# ST_LINK_Kenzhebek_Aituar.net
KiCad netlist of a schematic drawn in Altium Designer
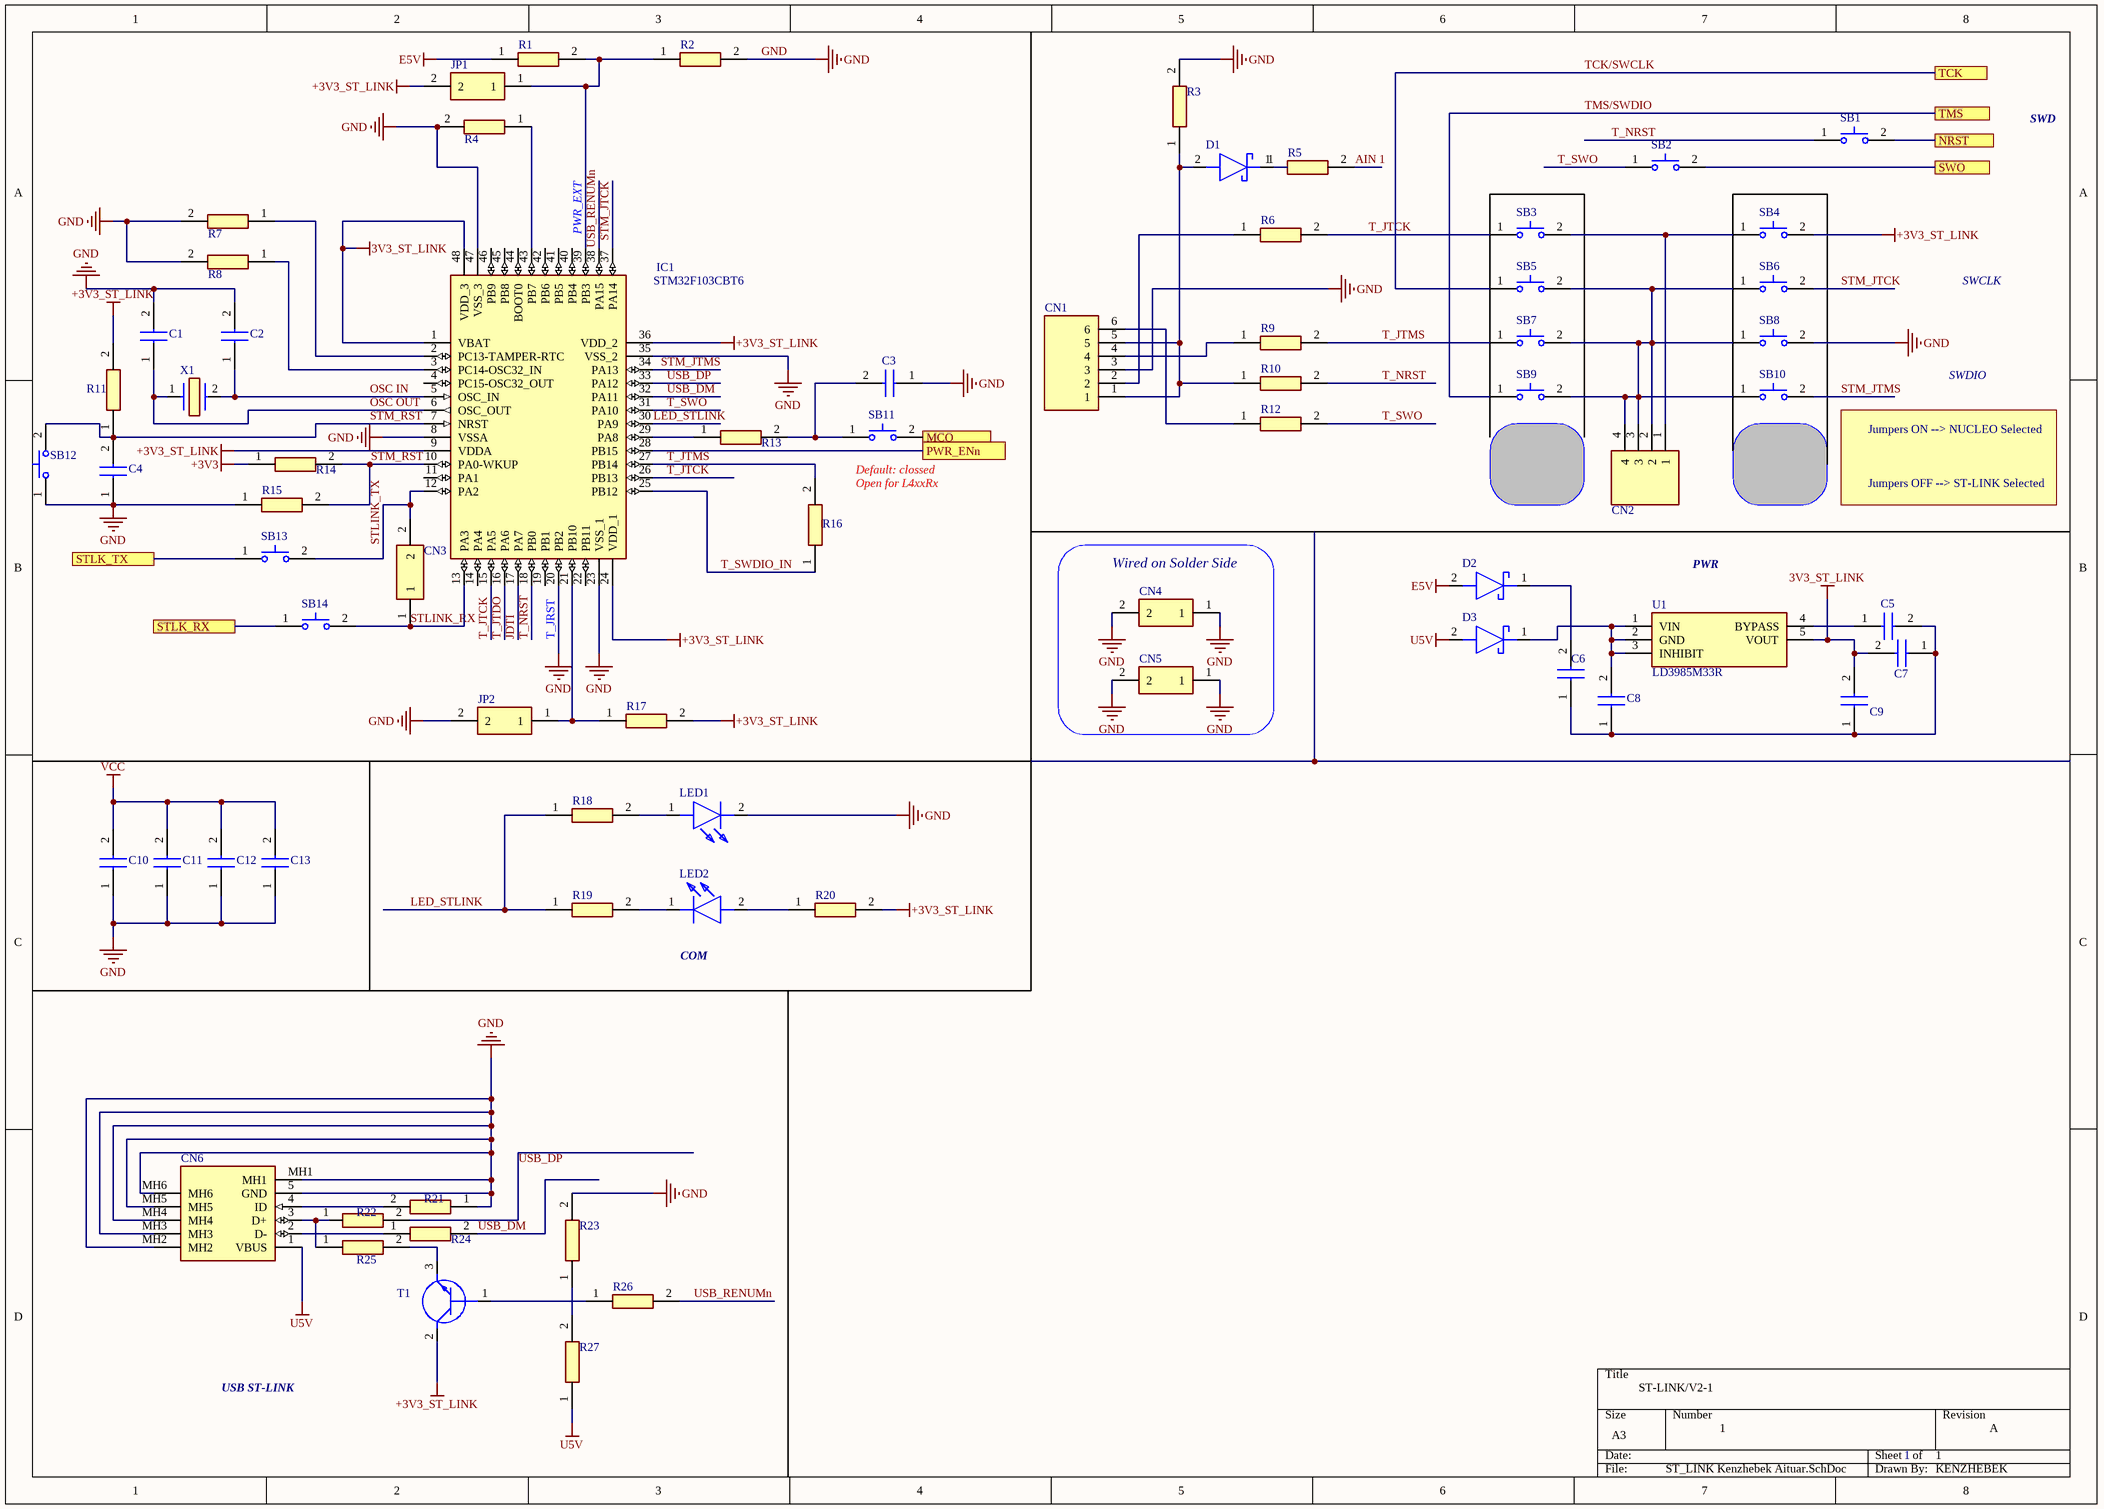
[diagram p0: ST_LINK Kenzhebek Aituar.SchDoc]

(export (version "E")
  (design (tool "Eeschema 10.0.6"))
  (components
    (comp (ref "C1")
      (value "C1206C200KCGACTU")
      (footprint "SamacSys:C1206")
      (description "Capacitor")
      (libsource (lib "*") (part "C1206C200KCGACTU"))
    )
    (comp (ref "C2")
      (value "C1206C200KCGACTU")
      (footprint "SamacSys:C1206")
      (description "Capacitor")
      (libsource (lib "*") (part "C1206C200KCGACTU"))
    )
    (comp (ref "C3")
      (value "C1206C200KCGACTU")
      (footprint "SamacSys:C1206")
      (description "Capacitor")
      (libsource (lib "*") (part "C1206C200KCGACTU"))
    )
    (comp (ref "C4")
      (value "KAM15AR71H104KM")
      (footprint "SamacSys:CAPC1608X90N")
      (description "Capacitor")
      (fields (field (name "MOUSER PART NUMBER") "581-KAM15AR71H104KM"))
      (libsource (lib "*") (part "KAM15AR71H104KM"))
    )
    (comp (ref "C5")
      (value "KGM31GCG2J103JU")
      (footprint "SamacSys:CAPC3316X145N")
      (description "Capacitor")
      (fields (field (name "MOUSER PART NUMBER") "581-KGM31GCG2J103JU"))
      (libsource (lib "*") (part "KGM31GCG2J103JU"))
    )
    (comp (ref "C6")
      (value "MAJCT168BB7105KTEA01")
      (footprint "SamacSys:MAJx16")
      (description "Capacitor")
      (libsource (lib "*") (part "MAJCT168BB7105KTEA01"))
    )
    (comp (ref "C7")
      (value "KAM15AR71H104KM")
      (footprint "SamacSys:CAPC1608X90N")
      (description "Capacitor")
      (fields (field (name "MOUSER PART NUMBER") "581-KAM15AR71H104KM"))
      (libsource (lib "*") (part "KAM15AR71H104KM"))
    )
    (comp (ref "C8")
      (value "KAM15AR71H104KM")
      (footprint "SamacSys:CAPC1608X90N")
      (description "Capacitor")
      (fields (field (name "MOUSER PART NUMBER") "581-KAM15AR71H104KM"))
      (libsource (lib "*") (part "KAM15AR71H104KM"))
    )
    (comp (ref "C9")
      (value "MAJCT168BB7105KTEA01")
      (footprint "SamacSys:MAJx16")
      (description "Capacitor")
      (libsource (lib "*") (part "MAJCT168BB7105KTEA01"))
    )
    (comp (ref "C10")
      (value "KAM15AR71H104KM")
      (footprint "SamacSys:CAPC1608X90N")
      (description "Capacitor")
      (fields (field (name "MOUSER PART NUMBER") "581-KAM15AR71H104KM"))
      (libsource (lib "*") (part "KAM15AR71H104KM"))
    )
    (comp (ref "C11")
      (value "KAM15AR71H104KM")
      (footprint "SamacSys:CAPC1608X90N")
      (description "Capacitor")
      (fields (field (name "MOUSER PART NUMBER") "581-KAM15AR71H104KM"))
      (libsource (lib "*") (part "KAM15AR71H104KM"))
    )
    (comp (ref "C12")
      (value "KAM15AR71H104KM")
      (footprint "SamacSys:CAPC1608X90N")
      (description "Capacitor")
      (fields (field (name "MOUSER PART NUMBER") "581-KAM15AR71H104KM"))
      (libsource (lib "*") (part "KAM15AR71H104KM"))
    )
    (comp (ref "C13")
      (value "KAM15AR71H104KM")
      (footprint "SamacSys:CAPC1608X90N")
      (description "Capacitor")
      (fields (field (name "MOUSER PART NUMBER") "581-KAM15AR71H104KM"))
      (libsource (lib "*") (part "KAM15AR71H104KM"))
    )
    (comp (ref "CN1")
      (value "22-28-4062")
      (footprint "SamacSys:HDRV6W66P0X254_1X6_1524X249X838P")
      (description "Connector")
      (fields (field (name "MOUSER PART NUMBER") "538-22-28-4062"))
      (libsource (lib "*") (part "22-28-4062"))
    )
    (comp (ref "CN2")
      (value "53014-0410")
      (footprint "SamacSys:SHDR4W60P0X200_1X4_1200X435X1000P")
      (description "Connector")
      (fields (field (name "MOUSER PART NUMBER") "538-53014-0410"))
      (libsource (lib "*") (part "53014-0410"))
    )
    (comp (ref "CN3")
      (value "3-647166-2")
      (footprint "SamacSys:36471662")
      (description "Connector")
      (fields (field (name "MOUSER PART NUMBER") "571-3-647166-2"))
      (libsource (lib "*") (part "3-647166-2"))
    )
    (comp (ref "CN4")
      (value "3-647166-2")
      (footprint "SamacSys:36471662")
      (description "Connector")
      (fields (field (name "MOUSER PART NUMBER") "571-3-647166-2"))
      (libsource (lib "") (part "3-647166-2_1"))
    )
    (comp (ref "CN5")
      (value "3-647166-2")
      (footprint "SamacSys:36471662")
      (description "Connector")
      (fields (field (name "MOUSER PART NUMBER") "571-3-647166-2"))
      (libsource (lib "") (part "3-647166-2_1"))
    )
    (comp (ref "CN6")
      (value "204926-1103")
      (footprint "SamacSys:2049261103")
      (description "Connector")
      (fields (field (name "MOUSER PART NUMBER") "538-204926-1103"))
      (libsource (lib "*") (part "204926-1103"))
    )
    (comp (ref "D1")
      (value "BAT60JFILM")
      (footprint "SamacSys:SOD2513X117N")
      (description "Schottky Diode")
      (fields (field (name "MOUSER PART NUMBER") "511-BAT60JFILM"))
      (libsource (lib "*") (part "BAT60JFILM"))
    )
    (comp (ref "D2")
      (value "BAT60JFILM")
      (footprint "SamacSys:SOD2513X117N")
      (description "Schottky Diode")
      (fields (field (name "MOUSER PART NUMBER") "511-BAT60JFILM"))
      (libsource (lib "*") (part "BAT60JFILM"))
    )
    (comp (ref "D3")
      (value "BAT60JFILM")
      (footprint "SamacSys:SOD2513X117N")
      (description "Schottky Diode")
      (fields (field (name "MOUSER PART NUMBER") "511-BAT60JFILM"))
      (libsource (lib "*") (part "BAT60JFILM"))
    )
    (comp (ref "IC1")
      (value "STM32F103CBT6")
      (footprint "SamacSys:QFP50P900X900X160-48N")
      (description "Integrated Circuit")
      (fields (field (name "MOUSER PART NUMBER") "511-STM32F103CBT6"))
      (libsource (lib "*") (part "STM32F103CBT6"))
    )
    (comp (ref "JP1")
      (value "3-647166-2")
      (footprint "SamacSys:36471662")
      (description "Connector")
      (fields (field (name "MOUSER PART NUMBER") "571-3-647166-2"))
      (libsource (lib "") (part "3-647166-2_1"))
    )
    (comp (ref "JP2")
      (value "3-647166-2")
      (footprint "SamacSys:36471662")
      (description "Connector")
      (fields (field (name "MOUSER PART NUMBER") "571-3-647166-2"))
      (libsource (lib "") (part "3-647166-2_1"))
    )
    (comp (ref "LED1")
      (value "C4SMA-RGY-CS4V1BB1")
      (footprint "SamacSys:C4SMARGYCS4V1BB1")
      (description "LED")
      (fields (field (name "MOUSER PART NUMBER") "941-C4SMARGYCS4V1BB1"))
      (libsource (lib "*") (part "C4SMA-RGY-CS4V1BB1"))
    )
    (comp (ref "LED2")
      (value "TLHG5420-ASZ")
      (footprint "SamacSys:TLHG5420ASZ")
      (description "LED")
      (fields (field (name "MOUSER PART NUMBER") "78-TLHG5420-ASZ"))
      (libsource (lib "*") (part "TLHG5420-ASZ"))
    )
    (comp (ref "R1")
      (value "ERA-6ARB272V")
      (footprint "SamacSys:ERA6AEB1020V")
      (description "Resistor")
      (fields (field (name "MOUSER PART NUMBER") "667-ERA-6ARB272V"))
      (libsource (lib "*") (part "ERA-6ARB272V"))
    )
    (comp (ref "R2")
      (value "MCS04020D4701BE000")
      (footprint "SamacSys:RESC1005X37N")
      (description "Resistor")
      (fields (field (name "MOUSER PART NUMBER") "594-MCS04020D4701BE0"))
      (libsource (lib "*") (part "MCS04020D4701BE000"))
    )
    (comp (ref "R3")
      (value "CRM2512QJW-103ELF")
      (footprint "SamacSys:RESC6331X80N")
      (description "Resistor")
      (fields (field (name "MOUSER PART NUMBER") "652-CRM2512QJW-103E"))
      (libsource (lib "") (part "CRM2512QJW-103ELF_1"))
    )
    (comp (ref "R4")
      (value "SFR01MZPF1003")
      (footprint "SamacSys:RESC1005X40N")
      (description "Resistor")
      (fields (field (name "MOUSER PART NUMBER") "755-SFR01MZPF1003"))
      (libsource (lib "*") (part "SFR01MZPF1003"))
    )
    (comp (ref "R5")
      (value "MCS04020C1000FE000")
      (footprint "SamacSys:RESC1005X37N")
      (description "Resistor")
      (fields (field (name "MOUSER PART NUMBER") "594-MCS04020C1000FE0"))
      (libsource (lib "") (part "MCS04020C1000FE000_1"))
    )
    (comp (ref "R6")
      (value "ERA-6AHD220V")
      (footprint "SamacSys:ERA6AEB1020V")
      (description "Resistor")
      (fields (field (name "MOUSER PART NUMBER") "667-ERA-6AHD220V"))
      (libsource (lib "*") (part "ERA-6AHD220V"))
    )
    (comp (ref "R7")
      (value "CRM2512QJW-103ELF")
      (footprint "SamacSys:RESC6331X80N")
      (description "Resistor")
      (fields (field (name "MOUSER PART NUMBER") "652-CRM2512QJW-103E"))
      (libsource (lib "*") (part "CRM2512QJW-103ELF"))
    )
    (comp (ref "R8")
      (value "CRM2512QJW-103ELF")
      (footprint "SamacSys:RESC6331X80N")
      (description "Resistor")
      (fields (field (name "MOUSER PART NUMBER") "652-CRM2512QJW-103E"))
      (libsource (lib "*") (part "CRM2512QJW-103ELF"))
    )
    (comp (ref "R9")
      (value "ERA-6AHD220V")
      (footprint "SamacSys:ERA6AEB1020V")
      (description "Resistor")
      (fields (field (name "MOUSER PART NUMBER") "667-ERA-6AHD220V"))
      (libsource (lib "*") (part "ERA-6AHD220V"))
    )
    (comp (ref "R10")
      (value "ERA-6AHD220V")
      (footprint "SamacSys:ERA6AEB1020V")
      (description "Resistor")
      (fields (field (name "MOUSER PART NUMBER") "667-ERA-6AHD220V"))
      (libsource (lib "*") (part "ERA-6AHD220V"))
    )
    (comp (ref "R11")
      (value "SFR01MZPF1003")
      (footprint "SamacSys:RESC1005X40N")
      (description "Resistor")
      (fields (field (name "MOUSER PART NUMBER") "755-SFR01MZPF1003"))
      (libsource (lib "") (part "SFR01MZPF1003_1"))
    )
    (comp (ref "R12")
      (value "ERA-6AHD220V")
      (footprint "SamacSys:ERA6AEB1020V")
      (description "Resistor")
      (fields (field (name "MOUSER PART NUMBER") "667-ERA-6AHD220V"))
      (libsource (lib "*") (part "ERA-6AHD220V"))
    )
    (comp (ref "R13")
      (value "MCS04020C1000FE000")
      (footprint "SamacSys:RESC1005X37N")
      (description "Resistor")
      (fields (field (name "MOUSER PART NUMBER") "594-MCS04020C1000FE0"))
      (libsource (lib "") (part "MCS04020C1000FE000_1"))
    )
    (comp (ref "R14")
      (value "MCS04020D4701BE000")
      (footprint "SamacSys:RESC1005X37N")
      (description "Resistor")
      (fields (field (name "MOUSER PART NUMBER") "594-MCS04020D4701BE0"))
      (libsource (lib "*") (part "MCS04020D4701BE000"))
    )
    (comp (ref "R15")
      (value "MCS04020D4701BE000")
      (footprint "SamacSys:RESC1005X37N")
      (description "Resistor")
      (fields (field (name "MOUSER PART NUMBER") "594-MCS04020D4701BE0"))
      (libsource (lib "*") (part "MCS04020D4701BE000"))
    )
    (comp (ref "R16")
      (value "MCS04020C1000FE000")
      (footprint "SamacSys:RESC1005X37N")
      (description "Resistor")
      (fields (field (name "MOUSER PART NUMBER") "594-MCS04020C1000FE0"))
      (libsource (lib "*") (part "MCS04020C1000FE000"))
    )
    (comp (ref "R17")
      (value "WSL080500000ZEA9")
      (footprint "SamacSys:RESC2013X84N")
      (description "Resistor")
      (fields (field (name "MOUSER PART NUMBER") "71-WSL080500000ZEA9"))
      (libsource (lib "*") (part "WSL080500000ZEA9"))
    )
    (comp (ref "R18")
      (value "MCS04020C1000FE000")
      (footprint "SamacSys:RESC1005X37N")
      (description "Resistor")
      (fields (field (name "MOUSER PART NUMBER") "594-MCS04020C1000FE0"))
      (libsource (lib "") (part "MCS04020C1000FE000_1"))
    )
    (comp (ref "R19")
      (value "MCS04020C1000FE000")
      (footprint "SamacSys:RESC1005X37N")
      (description "Resistor")
      (fields (field (name "MOUSER PART NUMBER") "594-MCS04020C1000FE0"))
      (libsource (lib "") (part "MCS04020C1000FE000_1"))
    )
    (comp (ref "R20")
      (value "WSL080500000ZEA9")
      (footprint "SamacSys:RESC2013X84N")
      (description "Resistor")
      (fields (field (name "MOUSER PART NUMBER") "71-WSL080500000ZEA9"))
      (libsource (lib "*") (part "WSL080500000ZEA9"))
    )
    (comp (ref "R21")
      (value "SFR01MZPF1003")
      (footprint "SamacSys:RESC1005X40N")
      (description "Resistor")
      (fields (field (name "MOUSER PART NUMBER") "755-SFR01MZPF1003"))
      (libsource (lib "*") (part "SFR01MZPF1003"))
    )
    (comp (ref "R22")
      (value "WSL080500000ZEA9")
      (footprint "SamacSys:RESC2013X84N")
      (description "Resistor")
      (fields (field (name "MOUSER PART NUMBER") "71-WSL080500000ZEA9"))
      (libsource (lib "*") (part "WSL080500000ZEA9"))
    )
    (comp (ref "R23")
      (value "TNPW080536K0BEEA")
      (footprint "SamacSys:RESC2012X55N")
      (description "Resistor")
      (libsource (lib "*") (part "TNPW080536K0BEEA"))
    )
    (comp (ref "R24")
      (value "WSL080500000ZEA9")
      (footprint "SamacSys:RESC2013X84N")
      (description "Resistor")
      (fields (field (name "MOUSER PART NUMBER") "71-WSL080500000ZEA9"))
      (libsource (lib "*") (part "WSL080500000ZEA9"))
    )
    (comp (ref "R25")
      (value "CRCW12102K70FKEAHP")
      (footprint "SamacSys:RESC3225X70N")
      (description "Resistor")
      (fields (field (name "MOUSER PART NUMBER") "71-CRCW12102K70FKEAH"))
      (libsource (lib "*") (part "CRCW12102K70FKEAHP"))
    )
    (comp (ref "R26")
      (value "MCS04020C1000FE000")
      (footprint "SamacSys:RESC1005X37N")
      (description "Resistor")
      (fields (field (name "MOUSER PART NUMBER") "594-MCS04020C1000FE0"))
      (libsource (lib "") (part "MCS04020C1000FE000_1"))
    )
    (comp (ref "R27")
      (value "CRM2512QJW-103ELF")
      (footprint "SamacSys:RESC6331X80N")
      (description "Resistor")
      (fields (field (name "MOUSER PART NUMBER") "652-CRM2512QJW-103E"))
      (libsource (lib "") (part "CRM2512QJW-103ELF_1"))
    )
    (comp (ref "SB1")
      (value "8631CQD2")
      (footprint "SamacSys:8631CQD2")
      (description "Switch (2-Pin Push)")
      (fields (field (name "MOUSER PART NUMBER") "611-8631-261"))
      (libsource (lib "*") (part "8631CQD2"))
    )
    (comp (ref "SB2")
      (value "8631CQD2")
      (footprint "SamacSys:8631CQD2")
      (description "Switch (2-Pin Push)")
      (fields (field (name "MOUSER PART NUMBER") "611-8631-261"))
      (libsource (lib "*") (part "8631CQD2"))
    )
    (comp (ref "SB3")
      (value "8631CQD2")
      (footprint "SamacSys:8631CQD2")
      (description "Switch (2-Pin Push)")
      (fields (field (name "MOUSER PART NUMBER") "611-8631-261"))
      (libsource (lib "*") (part "8631CQD2"))
    )
    (comp (ref "SB4")
      (value "8631CQD2")
      (footprint "SamacSys:8631CQD2")
      (description "Switch (2-Pin Push)")
      (fields (field (name "MOUSER PART NUMBER") "611-8631-261"))
      (libsource (lib "*") (part "8631CQD2"))
    )
    (comp (ref "SB5")
      (value "8631CQD2")
      (footprint "SamacSys:8631CQD2")
      (description "Switch (2-Pin Push)")
      (fields (field (name "MOUSER PART NUMBER") "611-8631-261"))
      (libsource (lib "*") (part "8631CQD2"))
    )
    (comp (ref "SB6")
      (value "8631CQD2")
      (footprint "SamacSys:8631CQD2")
      (description "Switch (2-Pin Push)")
      (fields (field (name "MOUSER PART NUMBER") "611-8631-261"))
      (libsource (lib "*") (part "8631CQD2"))
    )
    (comp (ref "SB7")
      (value "8631CQD2")
      (footprint "SamacSys:8631CQD2")
      (description "Switch (2-Pin Push)")
      (fields (field (name "MOUSER PART NUMBER") "611-8631-261"))
      (libsource (lib "*") (part "8631CQD2"))
    )
    (comp (ref "SB8")
      (value "8631CQD2")
      (footprint "SamacSys:8631CQD2")
      (description "Switch (2-Pin Push)")
      (fields (field (name "MOUSER PART NUMBER") "611-8631-261"))
      (libsource (lib "*") (part "8631CQD2"))
    )
    (comp (ref "SB9")
      (value "8631CQD2")
      (footprint "SamacSys:8631CQD2")
      (description "Switch (2-Pin Push)")
      (fields (field (name "MOUSER PART NUMBER") "611-8631-261"))
      (libsource (lib "*") (part "8631CQD2"))
    )
    (comp (ref "SB10")
      (value "8631CQD2")
      (footprint "SamacSys:8631CQD2")
      (description "Switch (2-Pin Push)")
      (fields (field (name "MOUSER PART NUMBER") "611-8631-261"))
      (libsource (lib "*") (part "8631CQD2"))
    )
    (comp (ref "SB11")
      (value "8631CQD2")
      (footprint "SamacSys:8631CQD2")
      (description "Switch (2-Pin Push)")
      (fields (field (name "MOUSER PART NUMBER") "611-8631-261"))
      (libsource (lib "*") (part "8631CQD2"))
    )
    (comp (ref "SB12")
      (value "8631CQD2")
      (footprint "SamacSys:8631CQD2")
      (description "Switch (2-Pin Push)")
      (fields (field (name "MOUSER PART NUMBER") "611-8631-261"))
      (libsource (lib "*") (part "8631CQD2"))
    )
    (comp (ref "SB13")
      (value "8631CQD2")
      (footprint "SamacSys:8631CQD2")
      (description "Switch (2-Pin Push)")
      (fields (field (name "MOUSER PART NUMBER") "611-8631-261"))
      (libsource (lib "*") (part "8631CQD2"))
    )
    (comp (ref "SB14")
      (value "8631CQD2")
      (footprint "SamacSys:8631CQD2")
      (description "Switch (2-Pin Push)")
      (fields (field (name "MOUSER PART NUMBER") "611-8631-261"))
      (libsource (lib "*") (part "8631CQD2"))
    )
    (comp (ref "T1")
      (value "BD139")
      (footprint "SamacSys:TO254P290X760X1320-3P")
      (description "Transistor BJT NPN")
      (fields (field (name "MOUSER PART NUMBER") "511-BD139"))
      (libsource (lib "*") (part "BD139"))
    )
    (comp (ref "U1")
      (value "LD3985M33R")
      (footprint "SamacSys:SOT95P280X145-5N")
      (description "Integrated Circuit")
      (fields (field (name "MOUSER PART NUMBER") "511-LD3985M33R"))
      (libsource (lib "*") (part "LD3985M33R"))
    )
    (comp (ref "X1")
      (value "ECS-80-12-5PX-GM-TR")
      (footprint "SamacSys:ECS80125PXGMTR")
      (description "Crystal or Oscillator")
      (fields (field (name "MOUSER PART NUMBER") "520-80-12-5PX-GM-TR"))
      (libsource (lib "*") (part "ECS-80-12-5PX-GM-TR"))
    )
  )
  (nets
    (net (code "1") (name "+3V3") (class "Default")
      (node (ref "R14") (pin "1") (pinfunction "1_1") (pintype "passive"))
    )
    (net (code "2") (name "+3V3_ST_LINK") (class "Default")
      (node (ref "IC1") (pin "24") (pinfunction "VDD_1_24") (pintype "passive"))
      (node (ref "IC1") (pin "36") (pinfunction "VDD_2_36") (pintype "passive"))
      (node (ref "IC1") (pin "9") (pinfunction "VDDA_9") (pintype "passive"))
      (node (ref "JP1") (pin "2") (pinfunction "2_2") (pintype "passive"))
      (node (ref "R11") (pin "2") (pinfunction "2_2") (pintype "passive"))
      (node (ref "R17") (pin "2") (pinfunction "2_2") (pintype "passive"))
      (node (ref "R20") (pin "2") (pinfunction "2_2") (pintype "passive"))
      (node (ref "SB4") (pin "2") (pinfunction "N.O._2_2") (pintype "passive"))
      (node (ref "T1") (pin "2") (pinfunction "C_2") (pintype "passive"))
    )
    (net (code "3") (name "/AIN 1") (class "Default")
      (node (ref "R5") (pin "2") (pinfunction "2_2") (pintype "passive"))
    )
    (net (code "4") (name "/JDTI") (class "Default")
      (node (ref "IC1") (pin "17") (pinfunction "PA7_17") (pintype "bidirectional"))
    )
    (net (code "5") (name "/LED_STLINK") (class "Default")
      (node (ref "IC1") (pin "30") (pinfunction "PA9_30") (pintype "bidirectional"))
      (node (ref "R18") (pin "1") (pinfunction "1_1") (pintype "passive"))
      (node (ref "R19") (pin "1") (pinfunction "1_1") (pintype "passive"))
    )
    (net (code "6") (name "/MCO") (class "Default")
      (node (ref "SB11") (pin "2") (pinfunction "N.O._2_2") (pintype "passive"))
    )
    (net (code "7") (name "/NRST") (class "Default")
      (node (ref "SB1") (pin "2") (pinfunction "N.O._2_2") (pintype "passive"))
    )
    (net (code "8") (name "/OSC IN") (class "Default")
      (node (ref "C2") (pin "1") (pinfunction "1_1") (pintype "passive"))
      (node (ref "IC1") (pin "5") (pinfunction "OSC_IN_5") (pintype "input"))
      (node (ref "X1") (pin "2") (pinfunction "2_2") (pintype "passive"))
    )
    (net (code "9") (name "/OSC OUT") (class "Default")
      (node (ref "C1") (pin "1") (pinfunction "1_1") (pintype "passive"))
      (node (ref "IC1") (pin "6") (pinfunction "OSC_OUT_6") (pintype "output"))
      (node (ref "X1") (pin "1") (pinfunction "1_1") (pintype "passive"))
    )
    (net (code "10") (name "/PWR_ENn") (class "Default")
      (node (ref "IC1") (pin "28") (pinfunction "PB15_28") (pintype "bidirectional"))
    )
    (net (code "11") (name "/PWR_EXT") (class "Default")
      (node (ref "IC1") (pin "39") (pinfunction "PB3_39") (pintype "bidirectional"))
      (node (ref "JP1") (pin "1") (pinfunction "1_1") (pintype "passive"))
      (node (ref "R1") (pin "2") (pinfunction "2_2") (pintype "passive"))
      (node (ref "R2") (pin "1") (pinfunction "1_1") (pintype "passive"))
    )
    (net (code "12") (name "/STLINK_RX") (class "Default")
      (node (ref "CN3") (pin "1") (pinfunction "1_1") (pintype "passive"))
      (node (ref "IC1") (pin "13") (pinfunction "PA3_13") (pintype "bidirectional"))
      (node (ref "SB14") (pin "2") (pinfunction "N.O._2_2") (pintype "passive"))
    )
    (net (code "13") (name "/STLINK_TX") (class "Default")
      (node (ref "CN3") (pin "2") (pinfunction "2_2") (pintype "passive"))
      (node (ref "IC1") (pin "12") (pinfunction "PA2_12") (pintype "bidirectional"))
      (node (ref "SB13") (pin "2") (pinfunction "N.O._2_2") (pintype "passive"))
    )
    (net (code "14") (name "/STLK_RX") (class "Default")
      (node (ref "SB14") (pin "1") (pinfunction "N.O._1_1") (pintype "passive"))
    )
    (net (code "15") (name "/STLK_TX") (class "Default")
      (node (ref "SB13") (pin "1") (pinfunction "N.O._1_1") (pintype "passive"))
    )
    (net (code "16") (name "/STM_JTCK") (class "Default")
      (node (ref "IC1") (pin "37") (pinfunction "PA14_37") (pintype "bidirectional"))
      (node (ref "SB6") (pin "2") (pinfunction "N.O._2_2") (pintype "passive"))
    )
    (net (code "17") (name "/STM_JTMS") (class "Default")
      (node (ref "IC1") (pin "34") (pinfunction "PA13_34") (pintype "bidirectional"))
      (node (ref "SB10") (pin "2") (pinfunction "N.O._2_2") (pintype "passive"))
    )
    (net (code "18") (name "/STM_RST") (class "Default")
      (node (ref "C4") (pin "2") (pinfunction "2_2") (pintype "passive"))
      (node (ref "IC1") (pin "10") (pinfunction "PA0-WKUP_10") (pintype "bidirectional"))
      (node (ref "IC1") (pin "7") (pinfunction "NRST_7") (pintype "input"))
      (node (ref "R11") (pin "1") (pinfunction "1_1") (pintype "passive"))
      (node (ref "R14") (pin "2") (pinfunction "2_2") (pintype "passive"))
      (node (ref "R15") (pin "2") (pinfunction "2_2") (pintype "passive"))
      (node (ref "SB12") (pin "2") (pinfunction "N.O._2_2") (pintype "passive"))
    )
    (net (code "19") (name "/SWO") (class "Default")
      (node (ref "SB2") (pin "2") (pinfunction "N.O._2_2") (pintype "passive"))
    )
    (net (code "20") (name "/TCK{slash}SWCLK") (class "Default")
      (node (ref "SB5") (pin "1") (pinfunction "N.O._1_1") (pintype "passive"))
    )
    (net (code "21") (name "/TMS{slash}SWDIO") (class "Default")
      (node (ref "SB9") (pin "1") (pinfunction "N.O._1_1") (pintype "passive"))
    )
    (net (code "22") (name "/T_JTCK") (class "Default")
      (node (ref "IC1") (pin "15") (pinfunction "PA5_15") (pintype "bidirectional"))
      (node (ref "IC1") (pin "26") (pinfunction "PB13_26") (pintype "bidirectional"))
      (node (ref "R6") (pin "2") (pinfunction "2_2") (pintype "passive"))
      (node (ref "SB3") (pin "1") (pinfunction "N.O._1_1") (pintype "passive"))
    )
    (net (code "23") (name "/T_JTDO") (class "Default")
      (node (ref "IC1") (pin "16") (pinfunction "PA6_16") (pintype "bidirectional"))
    )
    (net (code "24") (name "/T_JTMS") (class "Default")
      (node (ref "IC1") (pin "27") (pinfunction "PB14_27") (pintype "bidirectional"))
      (node (ref "R16") (pin "2") (pinfunction "2_2") (pintype "passive"))
      (node (ref "R9") (pin "2") (pinfunction "2_2") (pintype "passive"))
      (node (ref "SB7") (pin "1") (pinfunction "N.O._1_1") (pintype "passive"))
    )
    (net (code "25") (name "/T_NRST") (class "Default")
      (node (ref "IC1") (pin "18") (pinfunction "PB0_18") (pintype "bidirectional"))
      (node (ref "R10") (pin "2") (pinfunction "2_2") (pintype "passive"))
      (node (ref "SB1") (pin "1") (pinfunction "N.O._1_1") (pintype "passive"))
    )
    (net (code "26") (name "/T_SWDIO_IN") (class "Default")
      (node (ref "IC1") (pin "25") (pinfunction "PB12_25") (pintype "bidirectional"))
      (node (ref "R16") (pin "1") (pinfunction "1_1") (pintype "passive"))
    )
    (net (code "27") (name "/T_SWO") (class "Default")
      (node (ref "IC1") (pin "31") (pinfunction "PA10_31") (pintype "bidirectional"))
      (node (ref "R12") (pin "2") (pinfunction "2_2") (pintype "passive"))
      (node (ref "SB2") (pin "1") (pinfunction "N.O._1_1") (pintype "passive"))
    )
    (net (code "28") (name "/USB_DM") (class "Default")
      (node (ref "IC1") (pin "32") (pinfunction "PA11_32") (pintype "bidirectional"))
      (node (ref "R24") (pin "2") (pinfunction "2_2") (pintype "passive"))
    )
    (net (code "29") (name "/USB_DP") (class "Default")
      (node (ref "IC1") (pin "33") (pinfunction "PA12_33") (pintype "bidirectional"))
      (node (ref "R22") (pin "2") (pinfunction "2_2") (pintype "passive"))
    )
    (net (code "30") (name "/USB_RENUMn") (class "Default")
      (node (ref "IC1") (pin "38") (pinfunction "PA15_38") (pintype "bidirectional"))
      (node (ref "R26") (pin "2") (pinfunction "2_2") (pintype "passive"))
    )
    (net (code "31") (name "3V3_ST_LINK") (class "Default")
      (node (ref "C7") (pin "2") (pinfunction "2_2") (pintype "passive"))
      (node (ref "C9") (pin "2") (pinfunction "2_2") (pintype "passive"))
      (node (ref "IC1") (pin "1") (pinfunction "VBAT_1") (pintype "passive"))
      (node (ref "IC1") (pin "48") (pinfunction "VDD_3_48") (pintype "passive"))
      (node (ref "U1") (pin "5") (pinfunction "VOUT_5") (pintype "passive"))
    )
    (net (code "32") (name "E5V") (class "Default")
      (node (ref "D2") (pin "2") (pinfunction "A_2") (pintype "passive"))
      (node (ref "R1") (pin "1") (pinfunction "1_1") (pintype "passive"))
    )
    (net (code "33") (name "GND") (class "Default")
      (node (ref "C1") (pin "2") (pinfunction "2_2") (pintype "passive"))
      (node (ref "C10") (pin "1") (pinfunction "1_1") (pintype "passive"))
      (node (ref "C11") (pin "1") (pinfunction "1_1") (pintype "passive"))
      (node (ref "C12") (pin "1") (pinfunction "1_1") (pintype "passive"))
      (node (ref "C13") (pin "1") (pinfunction "1_1") (pintype "passive"))
      (node (ref "C2") (pin "2") (pinfunction "2_2") (pintype "passive"))
      (node (ref "C3") (pin "1") (pinfunction "1_1") (pintype "passive"))
      (node (ref "C4") (pin "1") (pinfunction "1_1") (pintype "passive"))
      (node (ref "CN1") (pin "3") (pinfunction "3_3") (pintype "passive"))
      (node (ref "CN4") (pin "1") (pinfunction "1_1") (pintype "passive"))
      (node (ref "CN4") (pin "2") (pinfunction "2_2") (pintype "passive"))
      (node (ref "CN5") (pin "1") (pinfunction "1_1") (pintype "passive"))
      (node (ref "CN5") (pin "2") (pinfunction "2_2") (pintype "passive"))
      (node (ref "CN6") (pin "5") (pinfunction "GND_5") (pintype "passive"))
      (node (ref "CN6") (pin "MH1") (pinfunction "MH1_MH1") (pintype "passive"))
      (node (ref "CN6") (pin "MH2") (pinfunction "MH2_MH2") (pintype "passive"))
      (node (ref "CN6") (pin "MH3") (pinfunction "MH3_MH3") (pintype "passive"))
      (node (ref "CN6") (pin "MH4") (pinfunction "MH4_MH4") (pintype "passive"))
      (node (ref "CN6") (pin "MH5") (pinfunction "MH5_MH5") (pintype "passive"))
      (node (ref "CN6") (pin "MH6") (pinfunction "MH6_MH6") (pintype "passive"))
      (node (ref "IC1") (pin "20") (pinfunction "PB2_20") (pintype "bidirectional"))
      (node (ref "IC1") (pin "23") (pinfunction "VSS_1_23") (pintype "passive"))
      (node (ref "IC1") (pin "35") (pinfunction "VSS_2_35") (pintype "passive"))
      (node (ref "IC1") (pin "47") (pinfunction "VSS_3_47") (pintype "passive"))
      (node (ref "IC1") (pin "8") (pinfunction "VSSA_8") (pintype "passive"))
      (node (ref "JP2") (pin "2") (pinfunction "2_2") (pintype "passive"))
      (node (ref "LED1") (pin "2") (pinfunction "K_2") (pintype "passive"))
      (node (ref "R15") (pin "1") (pinfunction "1_1") (pintype "passive"))
      (node (ref "R2") (pin "2") (pinfunction "2_2") (pintype "passive"))
      (node (ref "R21") (pin "1") (pinfunction "1_1") (pintype "passive"))
      (node (ref "R23") (pin "2") (pinfunction "2_2") (pintype "passive"))
      (node (ref "R3") (pin "2") (pinfunction "2_2") (pintype "passive"))
      (node (ref "R4") (pin "2") (pinfunction "2_2") (pintype "passive"))
      (node (ref "R7") (pin "2") (pinfunction "2_2") (pintype "passive"))
      (node (ref "R8") (pin "2") (pinfunction "2_2") (pintype "passive"))
      (node (ref "SB12") (pin "1") (pinfunction "N.O._1_1") (pintype "passive"))
      (node (ref "SB8") (pin "2") (pinfunction "N.O._2_2") (pintype "passive"))
    )
    (net (code "34") (name "Net-(C5-Pad2)") (class "Default")
      (node (ref "C5") (pin "2") (pinfunction "2_2") (pintype "passive"))
      (node (ref "C6") (pin "1") (pinfunction "1_1") (pintype "passive"))
      (node (ref "C7") (pin "1") (pinfunction "1_1") (pintype "passive"))
      (node (ref "C8") (pin "1") (pinfunction "1_1") (pintype "passive"))
      (node (ref "C9") (pin "1") (pinfunction "1_1") (pintype "passive"))
    )
    (net (code "35") (name "Net-(CN1-Pad2)") (class "Default")
      (node (ref "CN1") (pin "2") (pinfunction "2_2") (pintype "passive"))
      (node (ref "R6") (pin "1") (pinfunction "1_1") (pintype "passive"))
    )
    (net (code "36") (name "Net-(CN1-Pad4)") (class "Default")
      (node (ref "CN1") (pin "4") (pinfunction "4_4") (pintype "passive"))
      (node (ref "R9") (pin "1") (pinfunction "1_1") (pintype "passive"))
    )
    (net (code "37") (name "Net-(CN1-Pad6)") (class "Default")
      (node (ref "CN1") (pin "6") (pinfunction "6_6") (pintype "passive"))
      (node (ref "R12") (pin "1") (pinfunction "1_1") (pintype "passive"))
    )
    (net (code "38") (name "Net-(CN6-D+)") (class "Default")
      (node (ref "CN6") (pin "3") (pinfunction "D+_3") (pintype "bidirectional"))
      (node (ref "R22") (pin "1") (pinfunction "1_1") (pintype "passive"))
      (node (ref "R25") (pin "1") (pinfunction "1_1") (pintype "passive"))
    )
    (net (code "39") (name "Net-(CN6-D-)") (class "Default")
      (node (ref "CN6") (pin "2") (pinfunction "D-_2") (pintype "bidirectional"))
      (node (ref "R24") (pin "1") (pinfunction "1_1") (pintype "passive"))
    )
    (net (code "40") (name "Net-(CN6-ID)") (class "Default")
      (node (ref "CN6") (pin "4") (pinfunction "ID_4") (pintype "input"))
      (node (ref "R21") (pin "2") (pinfunction "2_2") (pintype "passive"))
    )
    (net (code "41") (name "Net-(D1-A)") (class "Default")
      (node (ref "CN1") (pin "1") (pinfunction "1_1") (pintype "passive"))
      (node (ref "CN1") (pin "5") (pinfunction "5_5") (pintype "passive"))
      (node (ref "D1") (pin "2") (pinfunction "A_2") (pintype "passive"))
      (node (ref "R10") (pin "1") (pinfunction "1_1") (pintype "passive"))
      (node (ref "R3") (pin "1") (pinfunction "1_1") (pintype "passive"))
    )
    (net (code "42") (name "Net-(D2-K)") (class "Default")
      (node (ref "C6") (pin "2") (pinfunction "2_2") (pintype "passive"))
      (node (ref "D2") (pin "1") (pinfunction "K_1") (pintype "passive"))
    )
    (net (code "43") (name "Net-(D3-K)") (class "Default")
      (node (ref "C8") (pin "2") (pinfunction "2_2") (pintype "passive"))
      (node (ref "D3") (pin "1") (pinfunction "K_1") (pintype "passive"))
      (node (ref "U1") (pin "1") (pinfunction "VIN_1") (pintype "passive"))
      (node (ref "U1") (pin "2") (pinfunction "GND_2") (pintype "passive"))
      (node (ref "U1") (pin "3") (pinfunction "INHIBIT_3") (pintype "passive"))
    )
    (net (code "44") (name "Net-(IC1-PA8)") (class "Default")
      (node (ref "IC1") (pin "29") (pinfunction "PA8_29") (pintype "bidirectional"))
      (node (ref "R13") (pin "1") (pinfunction "1_1") (pintype "passive"))
    )
    (net (code "45") (name "Net-(IC1-PB7)") (class "Default")
      (node (ref "IC1") (pin "43") (pinfunction "PB7_43") (pintype "bidirectional"))
      (node (ref "R4") (pin "1") (pinfunction "1_1") (pintype "passive"))
    )
    (net (code "46") (name "Net-(IC1-PB10)") (class "Default")
      (node (ref "IC1") (pin "21") (pinfunction "PB10_21") (pintype "bidirectional"))
      (node (ref "JP2") (pin "1") (pinfunction "1_1") (pintype "passive"))
      (node (ref "R17") (pin "1") (pinfunction "1_1") (pintype "passive"))
    )
    (net (code "47") (name "Net-(IC1-PC13-TAMPER-RTC)") (class "Default")
      (node (ref "IC1") (pin "2") (pinfunction "PC13-TAMPER-RTC_2") (pintype "bidirectional"))
      (node (ref "R7") (pin "1") (pinfunction "1_1") (pintype "passive"))
    )
    (net (code "48") (name "Net-(IC1-PC14-OSC32_IN)") (class "Default")
      (node (ref "IC1") (pin "3") (pinfunction "PC14-OSC32_IN_3") (pintype "bidirectional"))
      (node (ref "R8") (pin "1") (pinfunction "1_1") (pintype "passive"))
    )
    (net (code "49") (name "Net-(LED1-A)") (class "Default")
      (node (ref "LED1") (pin "1") (pinfunction "A_1") (pintype "passive"))
      (node (ref "R18") (pin "2") (pinfunction "2_2") (pintype "passive"))
    )
    (net (code "50") (name "Net-(LED2-A)") (class "Default")
      (node (ref "LED2") (pin "2") (pinfunction "A_2") (pintype "passive"))
      (node (ref "R20") (pin "1") (pinfunction "1_1") (pintype "passive"))
    )
    (net (code "51") (name "Net-(LED2-K)") (class "Default")
      (node (ref "LED2") (pin "1") (pinfunction "K_1") (pintype "passive"))
      (node (ref "R19") (pin "2") (pinfunction "2_2") (pintype "passive"))
    )
    (net (code "52") (name "Net-(R23-Pad1)") (class "Default")
      (node (ref "R23") (pin "1") (pinfunction "1_1") (pintype "passive"))
      (node (ref "R27") (pin "2") (pinfunction "2_2") (pintype "passive"))
    )
    (net (code "53") (name "Net-(SB3-N.O._2)") (class "Default")
      (node (ref "CN2") (pin "1") (pinfunction "1_1") (pintype "passive"))
      (node (ref "SB3") (pin "2") (pinfunction "N.O._2_2") (pintype "passive"))
      (node (ref "SB4") (pin "1") (pinfunction "N.O._1_1") (pintype "passive"))
    )
    (net (code "54") (name "Net-(SB10-N.O._1)") (class "Default")
      (node (ref "CN2") (pin "2") (pinfunction "2_2") (pintype "passive"))
      (node (ref "CN2") (pin "3") (pinfunction "3_3") (pintype "passive"))
      (node (ref "CN2") (pin "4") (pinfunction "4_4") (pintype "passive"))
      (node (ref "SB10") (pin "1") (pinfunction "N.O._1_1") (pintype "passive"))
      (node (ref "SB5") (pin "2") (pinfunction "N.O._2_2") (pintype "passive"))
      (node (ref "SB6") (pin "1") (pinfunction "N.O._1_1") (pintype "passive"))
      (node (ref "SB7") (pin "2") (pinfunction "N.O._2_2") (pintype "passive"))
      (node (ref "SB8") (pin "1") (pinfunction "N.O._1_1") (pintype "passive"))
      (node (ref "SB9") (pin "2") (pinfunction "N.O._2_2") (pintype "passive"))
    )
    (net (code "55") (name "Net-(SB11-N.O._1)") (class "Default")
      (node (ref "C3") (pin "2") (pinfunction "2_2") (pintype "passive"))
      (node (ref "R13") (pin "2") (pinfunction "2_2") (pintype "passive"))
      (node (ref "SB11") (pin "1") (pinfunction "N.O._1_1") (pintype "passive"))
    )
    (net (code "56") (name "Net-(T1-B)") (class "Default")
      (node (ref "R26") (pin "1") (pinfunction "1_1") (pintype "passive"))
      (node (ref "T1") (pin "1") (pinfunction "B_1") (pintype "passive"))
    )
    (net (code "57") (name "Net-(T1-E)") (class "Default")
      (node (ref "R25") (pin "2") (pinfunction "2_2") (pintype "passive"))
      (node (ref "T1") (pin "3") (pinfunction "E_3") (pintype "passive"))
    )
    (net (code "58") (name "Net-(U1-BYPASS)") (class "Default")
      (node (ref "C5") (pin "1") (pinfunction "1_1") (pintype "passive"))
      (node (ref "U1") (pin "4") (pinfunction "BYPASS_4") (pintype "passive"))
    )
    (net (code "59") (name "U5V") (class "Default")
      (node (ref "CN6") (pin "1") (pinfunction "VBUS_1") (pintype "passive"))
      (node (ref "D3") (pin "2") (pinfunction "A_2") (pintype "passive"))
      (node (ref "R27") (pin "1") (pinfunction "1_1") (pintype "passive"))
    )
    (net (code "60") (name "VCC") (class "Default")
      (node (ref "C10") (pin "2") (pinfunction "2_2") (pintype "passive"))
      (node (ref "C11") (pin "2") (pinfunction "2_2") (pintype "passive"))
      (node (ref "C12") (pin "2") (pinfunction "2_2") (pintype "passive"))
      (node (ref "C13") (pin "2") (pinfunction "2_2") (pintype "passive"))
    )
    (net (code "61") (name "unconnected-(D1-K-Pad1)") (class "Default")
      (node (ref "D1") (pin "1") (pinfunction "K_1") (pintype "passive"))
    )
    (net (code "62") (name "unconnected-(IC1-BOOT0-Pad44)") (class "Default")
      (node (ref "IC1") (pin "44") (pinfunction "BOOT0_44") (pintype "bidirectional"))
    )
    (net (code "63") (name "unconnected-(IC1-PA1-Pad11)") (class "Default")
      (node (ref "IC1") (pin "11") (pinfunction "PA1_11") (pintype "bidirectional"))
    )
    (net (code "64") (name "unconnected-(IC1-PA4-Pad14)") (class "Default")
      (node (ref "IC1") (pin "14") (pinfunction "PA4_14") (pintype "bidirectional"))
    )
    (net (code "65") (name "unconnected-(IC1-PB1-Pad19)") (class "Default")
      (node (ref "IC1") (pin "19") (pinfunction "PB1_19") (pintype "bidirectional"))
    )
    (net (code "66") (name "unconnected-(IC1-PB4-Pad40)") (class "Default")
      (node (ref "IC1") (pin "40") (pinfunction "PB4_40") (pintype "bidirectional"))
    )
    (net (code "67") (name "unconnected-(IC1-PB5-Pad41)") (class "Default")
      (node (ref "IC1") (pin "41") (pinfunction "PB5_41") (pintype "bidirectional"))
    )
    (net (code "68") (name "unconnected-(IC1-PB6-Pad42)") (class "Default")
      (node (ref "IC1") (pin "42") (pinfunction "PB6_42") (pintype "bidirectional"))
    )
    (net (code "69") (name "unconnected-(IC1-PB8-Pad45)") (class "Default")
      (node (ref "IC1") (pin "45") (pinfunction "PB8_45") (pintype "bidirectional"))
    )
    (net (code "70") (name "unconnected-(IC1-PB9-Pad46)") (class "Default")
      (node (ref "IC1") (pin "46") (pinfunction "PB9_46") (pintype "bidirectional"))
    )
    (net (code "71") (name "unconnected-(IC1-PB11-Pad22)") (class "Default")
      (node (ref "IC1") (pin "22") (pinfunction "PB11_22") (pintype "bidirectional"))
    )
    (net (code "72") (name "unconnected-(IC1-PC15-OSC32_OUT-Pad4)") (class "Default")
      (node (ref "IC1") (pin "4") (pinfunction "PC15-OSC32_OUT_4") (pintype "bidirectional"))
    )
    (net (code "73") (name "unconnected-(R5-Pad1)") (class "Default")
      (node (ref "R5") (pin "1") (pinfunction "1_1") (pintype "passive"))
    )
  )
)
